# 02-MIC.net
KiCad netlist of a schematic drawn in Altium Designer
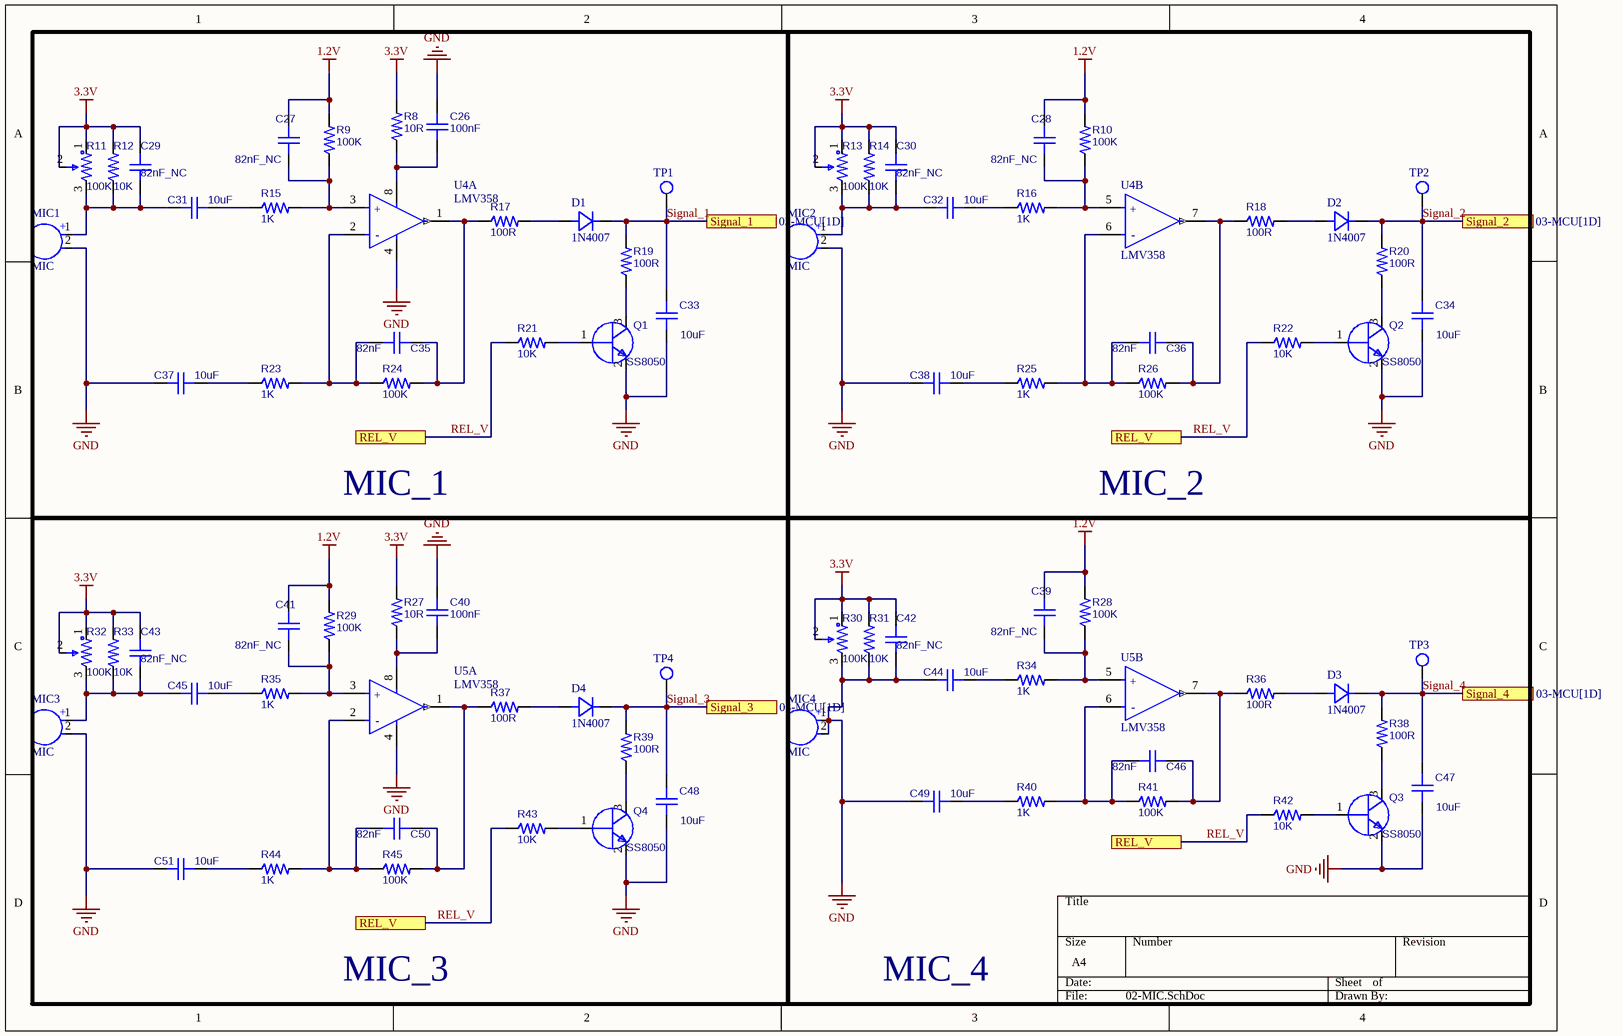
[diagram p0: 02-MIC.SchDoc]

(export (version "E")
  (design (tool "Eeschema 10.0.6"))
  (components
    (comp (ref "C26")
      (value "100nF")
      (footprint "CAP-SMD-0603")
      (description "贴片电容")
      (fields
        (field (name "BOM_MANUFACTURER PART") "CL03A104KQ3NNNC")
        (field (name "BOM_SUPPLIER PART") "C160831")
        (field (name "CONTRIBUTOR") "LCSC")
      )
      (libsource (lib "声源跟踪小车原理图库") (part "CAP"))
    )
    (comp (ref "C27")
      (value "82nF_NC")
      (footprint "CAP-SMD-0603")
      (description "贴片电容")
      (fields
        (field (name "BOM_MANUFACTURER PART") "CL03A104KQ3NNNC")
        (field (name "BOM_SUPPLIER PART") "C160831")
        (field (name "CONTRIBUTOR") "LCSC")
      )
      (libsource (lib "声源跟踪小车原理图库") (part "CAP"))
    )
    (comp (ref "C28")
      (value "82nF_NC")
      (footprint "CAP-SMD-0603")
      (description "贴片电容")
      (fields
        (field (name "BOM_MANUFACTURER PART") "CL03A104KQ3NNNC")
        (field (name "BOM_SUPPLIER PART") "C160831")
        (field (name "CONTRIBUTOR") "LCSC")
      )
      (libsource (lib "声源跟踪小车原理图库") (part "CAP"))
    )
    (comp (ref "C29")
      (value "82nF_NC")
      (footprint "CAP-SMD-0603")
      (description "贴片电容")
      (fields
        (field (name "BOM_MANUFACTURER PART") "CL03A104KQ3NNNC")
        (field (name "BOM_SUPPLIER PART") "C160831")
        (field (name "CONTRIBUTOR") "LCSC")
      )
      (libsource (lib "声源跟踪小车原理图库") (part "CAP"))
    )
    (comp (ref "C30")
      (value "82nF_NC")
      (footprint "CAP-SMD-0603")
      (description "贴片电容")
      (fields
        (field (name "BOM_MANUFACTURER PART") "CL03A104KQ3NNNC")
        (field (name "BOM_SUPPLIER PART") "C160831")
        (field (name "CONTRIBUTOR") "LCSC")
      )
      (libsource (lib "声源跟踪小车原理图库") (part "CAP"))
    )
    (comp (ref "C31")
      (value "10uF")
      (footprint "CAP-SMD-0603")
      (description "贴片电容")
      (fields
        (field (name "BOM_MANUFACTURER PART") "CL03A104KQ3NNNC")
        (field (name "BOM_SUPPLIER PART") "C160831")
        (field (name "CONTRIBUTOR") "LCSC")
      )
      (libsource (lib "声源跟踪小车原理图库") (part "CAP"))
    )
    (comp (ref "C32")
      (value "10uF")
      (footprint "CAP-SMD-0603")
      (description "贴片电容")
      (fields
        (field (name "BOM_MANUFACTURER PART") "CL03A104KQ3NNNC")
        (field (name "BOM_SUPPLIER PART") "C160831")
        (field (name "CONTRIBUTOR") "LCSC")
      )
      (libsource (lib "声源跟踪小车原理图库") (part "CAP"))
    )
    (comp (ref "C33")
      (value "10uF")
      (footprint "CAP-SMD-0603")
      (description "贴片电容")
      (fields
        (field (name "BOM_MANUFACTURER PART") "CL03A104KQ3NNNC")
        (field (name "BOM_SUPPLIER PART") "C160831")
        (field (name "CONTRIBUTOR") "LCSC")
      )
      (libsource (lib "声源跟踪小车原理图库") (part "CAP"))
    )
    (comp (ref "C34")
      (value "10uF")
      (footprint "CAP-SMD-0603")
      (description "贴片电容")
      (fields
        (field (name "BOM_MANUFACTURER PART") "CL03A104KQ3NNNC")
        (field (name "BOM_SUPPLIER PART") "C160831")
        (field (name "CONTRIBUTOR") "LCSC")
      )
      (libsource (lib "声源跟踪小车原理图库") (part "CAP"))
    )
    (comp (ref "C35")
      (value "82nF")
      (footprint "CAP-SMD-0603")
      (description "贴片电容")
      (fields
        (field (name "BOM_MANUFACTURER PART") "CL03A104KQ3NNNC")
        (field (name "BOM_SUPPLIER PART") "C160831")
        (field (name "CONTRIBUTOR") "LCSC")
      )
      (libsource (lib "声源跟踪小车原理图库") (part "CAP"))
    )
    (comp (ref "C36")
      (value "82nF")
      (footprint "CAP-SMD-0603")
      (description "贴片电容")
      (fields
        (field (name "BOM_MANUFACTURER PART") "CL03A104KQ3NNNC")
        (field (name "BOM_SUPPLIER PART") "C160831")
        (field (name "CONTRIBUTOR") "LCSC")
      )
      (libsource (lib "声源跟踪小车原理图库") (part "CAP"))
    )
    (comp (ref "C37")
      (value "10uF")
      (footprint "CAP-SMD-0603")
      (description "贴片电容")
      (fields
        (field (name "BOM_MANUFACTURER PART") "CL03A104KQ3NNNC")
        (field (name "BOM_SUPPLIER PART") "C160831")
        (field (name "CONTRIBUTOR") "LCSC")
      )
      (libsource (lib "声源跟踪小车原理图库") (part "CAP"))
    )
    (comp (ref "C38")
      (value "10uF")
      (footprint "CAP-SMD-0603")
      (description "贴片电容")
      (fields
        (field (name "BOM_MANUFACTURER PART") "CL03A104KQ3NNNC")
        (field (name "BOM_SUPPLIER PART") "C160831")
        (field (name "CONTRIBUTOR") "LCSC")
      )
      (libsource (lib "声源跟踪小车原理图库") (part "CAP"))
    )
    (comp (ref "C39")
      (value "82nF_NC")
      (footprint "CAP-SMD-0603")
      (description "贴片电容")
      (fields
        (field (name "BOM_MANUFACTURER PART") "CL03A104KQ3NNNC")
        (field (name "BOM_SUPPLIER PART") "C160831")
        (field (name "CONTRIBUTOR") "LCSC")
      )
      (libsource (lib "声源跟踪小车原理图库") (part "CAP"))
    )
    (comp (ref "C40")
      (value "100nF")
      (footprint "CAP-SMD-0603")
      (description "贴片电容")
      (fields
        (field (name "BOM_MANUFACTURER PART") "CL03A104KQ3NNNC")
        (field (name "BOM_SUPPLIER PART") "C160831")
        (field (name "CONTRIBUTOR") "LCSC")
      )
      (libsource (lib "声源跟踪小车原理图库") (part "CAP"))
    )
    (comp (ref "C41")
      (value "82nF_NC")
      (footprint "CAP-SMD-0603")
      (description "贴片电容")
      (fields
        (field (name "BOM_MANUFACTURER PART") "CL03A104KQ3NNNC")
        (field (name "BOM_SUPPLIER PART") "C160831")
        (field (name "CONTRIBUTOR") "LCSC")
      )
      (libsource (lib "声源跟踪小车原理图库") (part "CAP"))
    )
    (comp (ref "C42")
      (value "82nF_NC")
      (footprint "CAP-SMD-0603")
      (description "贴片电容")
      (fields
        (field (name "BOM_MANUFACTURER PART") "CL03A104KQ3NNNC")
        (field (name "BOM_SUPPLIER PART") "C160831")
        (field (name "CONTRIBUTOR") "LCSC")
      )
      (libsource (lib "声源跟踪小车原理图库") (part "CAP"))
    )
    (comp (ref "C43")
      (value "82nF_NC")
      (footprint "CAP-SMD-0603")
      (description "贴片电容")
      (fields
        (field (name "BOM_MANUFACTURER PART") "CL03A104KQ3NNNC")
        (field (name "BOM_SUPPLIER PART") "C160831")
        (field (name "CONTRIBUTOR") "LCSC")
      )
      (libsource (lib "声源跟踪小车原理图库") (part "CAP"))
    )
    (comp (ref "C44")
      (value "10uF")
      (footprint "CAP-SMD-0603")
      (description "贴片电容")
      (fields
        (field (name "BOM_MANUFACTURER PART") "CL03A104KQ3NNNC")
        (field (name "BOM_SUPPLIER PART") "C160831")
        (field (name "CONTRIBUTOR") "LCSC")
      )
      (libsource (lib "声源跟踪小车原理图库") (part "CAP"))
    )
    (comp (ref "C45")
      (value "10uF")
      (footprint "CAP-SMD-0603")
      (description "贴片电容")
      (fields
        (field (name "BOM_MANUFACTURER PART") "CL03A104KQ3NNNC")
        (field (name "BOM_SUPPLIER PART") "C160831")
        (field (name "CONTRIBUTOR") "LCSC")
      )
      (libsource (lib "声源跟踪小车原理图库") (part "CAP"))
    )
    (comp (ref "C46")
      (value "82nF")
      (footprint "CAP-SMD-0603")
      (description "贴片电容")
      (fields
        (field (name "BOM_MANUFACTURER PART") "CL03A104KQ3NNNC")
        (field (name "BOM_SUPPLIER PART") "C160831")
        (field (name "CONTRIBUTOR") "LCSC")
      )
      (libsource (lib "声源跟踪小车原理图库") (part "CAP"))
    )
    (comp (ref "C47")
      (value "10uF")
      (footprint "CAP-SMD-0603")
      (description "贴片电容")
      (fields
        (field (name "BOM_MANUFACTURER PART") "CL03A104KQ3NNNC")
        (field (name "BOM_SUPPLIER PART") "C160831")
        (field (name "CONTRIBUTOR") "LCSC")
      )
      (libsource (lib "声源跟踪小车原理图库") (part "CAP"))
    )
    (comp (ref "C48")
      (value "10uF")
      (footprint "CAP-SMD-0603")
      (description "贴片电容")
      (fields
        (field (name "BOM_MANUFACTURER PART") "CL03A104KQ3NNNC")
        (field (name "BOM_SUPPLIER PART") "C160831")
        (field (name "CONTRIBUTOR") "LCSC")
      )
      (libsource (lib "声源跟踪小车原理图库") (part "CAP"))
    )
    (comp (ref "C49")
      (value "10uF")
      (footprint "CAP-SMD-0603")
      (description "贴片电容")
      (fields
        (field (name "BOM_MANUFACTURER PART") "CL03A104KQ3NNNC")
        (field (name "BOM_SUPPLIER PART") "C160831")
        (field (name "CONTRIBUTOR") "LCSC")
      )
      (libsource (lib "声源跟踪小车原理图库") (part "CAP"))
    )
    (comp (ref "C50")
      (value "82nF")
      (footprint "CAP-SMD-0603")
      (description "贴片电容")
      (fields
        (field (name "BOM_MANUFACTURER PART") "CL03A104KQ3NNNC")
        (field (name "BOM_SUPPLIER PART") "C160831")
        (field (name "CONTRIBUTOR") "LCSC")
      )
      (libsource (lib "声源跟踪小车原理图库") (part "CAP"))
    )
    (comp (ref "C51")
      (value "10uF")
      (footprint "CAP-SMD-0603")
      (description "贴片电容")
      (fields
        (field (name "BOM_MANUFACTURER PART") "CL03A104KQ3NNNC")
        (field (name "BOM_SUPPLIER PART") "C160831")
        (field (name "CONTRIBUTOR") "LCSC")
      )
      (libsource (lib "声源跟踪小车原理图库") (part "CAP"))
    )
    (comp (ref "D1")
      (value "1N4007")
      (footprint "SOD-123-P3.4")
      (description "二极管1N4148W")
      (fields (field (name "MANUFACTURER") "PSI(宝力芯)") (field (name "MANUFACTURER PART") "1N4148W"))
      (libsource (lib "声源跟踪小车原理图库") (part "Diode"))
    )
    (comp (ref "D2")
      (value "1N4007")
      (footprint "SOD-123-P3.4")
      (description "二极管1N4148W")
      (fields (field (name "MANUFACTURER") "PSI(宝力芯)") (field (name "MANUFACTURER PART") "1N4148W"))
      (libsource (lib "声源跟踪小车原理图库") (part "Diode"))
    )
    (comp (ref "D3")
      (value "1N4007")
      (footprint "SOD-123-P3.4")
      (description "二极管1N4148W")
      (fields (field (name "MANUFACTURER") "PSI(宝力芯)") (field (name "MANUFACTURER PART") "1N4148W"))
      (libsource (lib "声源跟踪小车原理图库") (part "Diode"))
    )
    (comp (ref "D4")
      (value "1N4007")
      (footprint "SOD-123-P3.4")
      (description "二极管1N4148W")
      (fields (field (name "MANUFACTURER") "PSI(宝力芯)") (field (name "MANUFACTURER PART") "1N4148W"))
      (libsource (lib "声源跟踪小车原理图库") (part "Diode"))
    )
    (comp (ref "MIC1")
      (value "MIC")
      (footprint "MIC-TH-BD4.0-P1.4")
      (description "咪头MIC COND ANALOG OMNI -38DB")
      (libsource (lib "声源跟踪小车原理图库") (part "MIC"))
    )
    (comp (ref "MIC2")
      (value "MIC")
      (footprint "MIC-TH-BD4.0-P1.4")
      (description "咪头MIC COND ANALOG OMNI -38DB")
      (libsource (lib "声源跟踪小车原理图库") (part "MIC"))
    )
    (comp (ref "MIC3")
      (value "MIC")
      (footprint "MIC-TH-BD4.0-P1.4")
      (description "咪头MIC COND ANALOG OMNI -38DB")
      (libsource (lib "声源跟踪小车原理图库") (part "MIC"))
    )
    (comp (ref "MIC4")
      (value "MIC")
      (footprint "MIC-TH-BD4.0-P1.4")
      (description "咪头MIC COND ANALOG OMNI -38DB")
      (libsource (lib "声源跟踪小车原理图库") (part "MIC"))
    )
    (comp (ref "Q1")
      (value "SS8050")
      (footprint "SOT-23-3-LP2.28-P1.91")
      (description "贴片NPN三极管")
      (fields
        (field (name "BOM_SUPPLIER PART") "C2898668")
        (field (name "BOM_MANUFACTURER PART") "S9013")
        (field (name "CONTRIBUTOR") "LCSC")
      )
      (libsource (lib "声源跟踪小车原理图库") (part "NPN-SOT-23-3"))
    )
    (comp (ref "Q2")
      (value "SS8050")
      (footprint "SOT-23-3-LP2.28-P1.91")
      (description "贴片NPN三极管")
      (fields
        (field (name "BOM_SUPPLIER PART") "C2898668")
        (field (name "BOM_MANUFACTURER PART") "S9013")
        (field (name "CONTRIBUTOR") "LCSC")
      )
      (libsource (lib "声源跟踪小车原理图库") (part "NPN-SOT-23-3"))
    )
    (comp (ref "Q3")
      (value "SS8050")
      (footprint "SOT-23-3-LP2.28-P1.91")
      (description "贴片NPN三极管")
      (fields
        (field (name "BOM_SUPPLIER PART") "C2898668")
        (field (name "BOM_MANUFACTURER PART") "S9013")
        (field (name "CONTRIBUTOR") "LCSC")
      )
      (libsource (lib "声源跟踪小车原理图库") (part "NPN-SOT-23-3"))
    )
    (comp (ref "Q4")
      (value "SS8050")
      (footprint "SOT-23-3-LP2.28-P1.91")
      (description "贴片NPN三极管")
      (fields
        (field (name "BOM_SUPPLIER PART") "C2898668")
        (field (name "BOM_MANUFACTURER PART") "S9013")
        (field (name "CONTRIBUTOR") "LCSC")
      )
      (libsource (lib "声源跟踪小车原理图库") (part "NPN-SOT-23-3"))
    )
    (comp (ref "R8")
      (value "10R")
      (footprint "RES-SMD-0603")
      (description "贴片电阻")
      (fields
        (field (name "BOM_SUPPLIER PART") "C118966")
        (field (name "BOM_MANUFACTURER PART") "3362P-1-104")
        (field (name "CONTRIBUTOR") "LCSC")
      )
      (libsource (lib "声源跟踪小车原理图库") (part "RES"))
    )
    (comp (ref "R9")
      (value "100K")
      (footprint "RES-SMD-0603")
      (description "贴片电阻")
      (fields
        (field (name "BOM_SUPPLIER PART") "C118966")
        (field (name "BOM_MANUFACTURER PART") "3362P-1-104")
        (field (name "CONTRIBUTOR") "LCSC")
      )
      (libsource (lib "声源跟踪小车原理图库") (part "RES"))
    )
    (comp (ref "R10")
      (value "100K")
      (footprint "RES-SMD-0603")
      (description "贴片电阻")
      (fields
        (field (name "BOM_SUPPLIER PART") "C118966")
        (field (name "BOM_MANUFACTURER PART") "3362P-1-104")
        (field (name "CONTRIBUTOR") "LCSC")
      )
      (libsource (lib "声源跟踪小车原理图库") (part "RES"))
    )
    (comp (ref "R11")
      (value "100K")
      (footprint "RES-SMD-ADJ-3224W")
      (description "可调电阻,电位器")
      (fields
        (field (name "BOM_SUPPLIER PART") "C118966")
        (field (name "BOM_MANUFACTURER PART") "3362P-1-104")
        (field (name "CONTRIBUTOR") "LCSC")
      )
      (libsource (lib "声源跟踪小车原理图库") (part "RES-ADJ"))
    )
    (comp (ref "R12")
      (value "10K")
      (footprint "RES-SMD-0603")
      (description "贴片电阻")
      (fields
        (field (name "BOM_SUPPLIER PART") "C118966")
        (field (name "BOM_MANUFACTURER PART") "3362P-1-104")
        (field (name "CONTRIBUTOR") "LCSC")
      )
      (libsource (lib "声源跟踪小车原理图库") (part "RES"))
    )
    (comp (ref "R13")
      (value "100K")
      (footprint "RES-SMD-ADJ-3224W")
      (description "可调电阻,电位器")
      (fields
        (field (name "BOM_SUPPLIER PART") "C118966")
        (field (name "BOM_MANUFACTURER PART") "3362P-1-104")
        (field (name "CONTRIBUTOR") "LCSC")
      )
      (libsource (lib "声源跟踪小车原理图库") (part "RES-ADJ"))
    )
    (comp (ref "R14")
      (value "10K")
      (footprint "RES-SMD-0603")
      (description "贴片电阻")
      (fields
        (field (name "BOM_SUPPLIER PART") "C118966")
        (field (name "BOM_MANUFACTURER PART") "3362P-1-104")
        (field (name "CONTRIBUTOR") "LCSC")
      )
      (libsource (lib "声源跟踪小车原理图库") (part "RES"))
    )
    (comp (ref "R15")
      (value "1K")
      (footprint "RES-SMD-0603")
      (description "贴片电阻")
      (fields
        (field (name "BOM_SUPPLIER PART") "C118966")
        (field (name "BOM_MANUFACTURER PART") "3362P-1-104")
        (field (name "CONTRIBUTOR") "LCSC")
      )
      (libsource (lib "声源跟踪小车原理图库") (part "RES"))
    )
    (comp (ref "R16")
      (value "1K")
      (footprint "RES-SMD-0603")
      (description "贴片电阻")
      (fields
        (field (name "BOM_SUPPLIER PART") "C118966")
        (field (name "BOM_MANUFACTURER PART") "3362P-1-104")
        (field (name "CONTRIBUTOR") "LCSC")
      )
      (libsource (lib "声源跟踪小车原理图库") (part "RES"))
    )
    (comp (ref "R17")
      (value "100R")
      (footprint "RES-SMD-0603")
      (description "贴片电阻")
      (fields
        (field (name "BOM_SUPPLIER PART") "C118966")
        (field (name "BOM_MANUFACTURER PART") "3362P-1-104")
        (field (name "CONTRIBUTOR") "LCSC")
      )
      (libsource (lib "声源跟踪小车原理图库") (part "RES"))
    )
    (comp (ref "R18")
      (value "100R")
      (footprint "RES-SMD-0603")
      (description "贴片电阻")
      (fields
        (field (name "BOM_SUPPLIER PART") "C118966")
        (field (name "BOM_MANUFACTURER PART") "3362P-1-104")
        (field (name "CONTRIBUTOR") "LCSC")
      )
      (libsource (lib "声源跟踪小车原理图库") (part "RES"))
    )
    (comp (ref "R19")
      (value "100R")
      (footprint "RES-SMD-0603")
      (description "贴片电阻")
      (fields
        (field (name "BOM_SUPPLIER PART") "C118966")
        (field (name "BOM_MANUFACTURER PART") "3362P-1-104")
        (field (name "CONTRIBUTOR") "LCSC")
      )
      (libsource (lib "声源跟踪小车原理图库") (part "RES"))
    )
    (comp (ref "R20")
      (value "100R")
      (footprint "RES-SMD-0603")
      (description "贴片电阻")
      (fields
        (field (name "BOM_SUPPLIER PART") "C118966")
        (field (name "BOM_MANUFACTURER PART") "3362P-1-104")
        (field (name "CONTRIBUTOR") "LCSC")
      )
      (libsource (lib "声源跟踪小车原理图库") (part "RES"))
    )
    (comp (ref "R21")
      (value "10K")
      (footprint "RES-SMD-0603")
      (description "贴片电阻")
      (fields
        (field (name "BOM_SUPPLIER PART") "C118966")
        (field (name "BOM_MANUFACTURER PART") "3362P-1-104")
        (field (name "CONTRIBUTOR") "LCSC")
      )
      (libsource (lib "声源跟踪小车原理图库") (part "RES"))
    )
    (comp (ref "R22")
      (value "10K")
      (footprint "RES-SMD-0603")
      (description "贴片电阻")
      (fields
        (field (name "BOM_SUPPLIER PART") "C118966")
        (field (name "BOM_MANUFACTURER PART") "3362P-1-104")
        (field (name "CONTRIBUTOR") "LCSC")
      )
      (libsource (lib "声源跟踪小车原理图库") (part "RES"))
    )
    (comp (ref "R23")
      (value "1K")
      (footprint "RES-SMD-0603")
      (description "贴片电阻")
      (fields
        (field (name "BOM_SUPPLIER PART") "C118966")
        (field (name "BOM_MANUFACTURER PART") "3362P-1-104")
        (field (name "CONTRIBUTOR") "LCSC")
      )
      (libsource (lib "声源跟踪小车原理图库") (part "RES"))
    )
    (comp (ref "R24")
      (value "100K")
      (footprint "RES-SMD-0603")
      (description "贴片电阻")
      (fields
        (field (name "BOM_SUPPLIER PART") "C118966")
        (field (name "BOM_MANUFACTURER PART") "3362P-1-104")
        (field (name "CONTRIBUTOR") "LCSC")
      )
      (libsource (lib "声源跟踪小车原理图库") (part "RES"))
    )
    (comp (ref "R25")
      (value "1K")
      (footprint "RES-SMD-0603")
      (description "贴片电阻")
      (fields
        (field (name "BOM_SUPPLIER PART") "C118966")
        (field (name "BOM_MANUFACTURER PART") "3362P-1-104")
        (field (name "CONTRIBUTOR") "LCSC")
      )
      (libsource (lib "声源跟踪小车原理图库") (part "RES"))
    )
    (comp (ref "R26")
      (value "100K")
      (footprint "RES-SMD-0603")
      (description "贴片电阻")
      (fields
        (field (name "BOM_SUPPLIER PART") "C118966")
        (field (name "BOM_MANUFACTURER PART") "3362P-1-104")
        (field (name "CONTRIBUTOR") "LCSC")
      )
      (libsource (lib "声源跟踪小车原理图库") (part "RES"))
    )
    (comp (ref "R27")
      (value "10R")
      (footprint "RES-SMD-0603")
      (description "贴片电阻")
      (fields
        (field (name "BOM_SUPPLIER PART") "C118966")
        (field (name "BOM_MANUFACTURER PART") "3362P-1-104")
        (field (name "CONTRIBUTOR") "LCSC")
      )
      (libsource (lib "声源跟踪小车原理图库") (part "RES"))
    )
    (comp (ref "R28")
      (value "100K")
      (footprint "RES-SMD-0603")
      (description "贴片电阻")
      (fields
        (field (name "BOM_SUPPLIER PART") "C118966")
        (field (name "BOM_MANUFACTURER PART") "3362P-1-104")
        (field (name "CONTRIBUTOR") "LCSC")
      )
      (libsource (lib "声源跟踪小车原理图库") (part "RES"))
    )
    (comp (ref "R29")
      (value "100K")
      (footprint "RES-SMD-0603")
      (description "贴片电阻")
      (fields
        (field (name "BOM_SUPPLIER PART") "C118966")
        (field (name "BOM_MANUFACTURER PART") "3362P-1-104")
        (field (name "CONTRIBUTOR") "LCSC")
      )
      (libsource (lib "声源跟踪小车原理图库") (part "RES"))
    )
    (comp (ref "R30")
      (value "100K")
      (footprint "RES-SMD-ADJ-3224W")
      (description "可调电阻,电位器")
      (fields
        (field (name "BOM_SUPPLIER PART") "C118966")
        (field (name "BOM_MANUFACTURER PART") "3362P-1-104")
        (field (name "CONTRIBUTOR") "LCSC")
      )
      (libsource (lib "声源跟踪小车原理图库") (part "RES-ADJ"))
    )
    (comp (ref "R31")
      (value "10K")
      (footprint "RES-SMD-0603")
      (description "贴片电阻")
      (fields
        (field (name "BOM_SUPPLIER PART") "C118966")
        (field (name "BOM_MANUFACTURER PART") "3362P-1-104")
        (field (name "CONTRIBUTOR") "LCSC")
      )
      (libsource (lib "声源跟踪小车原理图库") (part "RES"))
    )
    (comp (ref "R32")
      (value "100K")
      (footprint "RES-SMD-ADJ-3224W")
      (description "可调电阻,电位器")
      (fields
        (field (name "BOM_SUPPLIER PART") "C118966")
        (field (name "BOM_MANUFACTURER PART") "3362P-1-104")
        (field (name "CONTRIBUTOR") "LCSC")
      )
      (libsource (lib "声源跟踪小车原理图库") (part "RES-ADJ"))
    )
    (comp (ref "R33")
      (value "10K")
      (footprint "RES-SMD-0603")
      (description "贴片电阻")
      (fields
        (field (name "BOM_SUPPLIER PART") "C118966")
        (field (name "BOM_MANUFACTURER PART") "3362P-1-104")
        (field (name "CONTRIBUTOR") "LCSC")
      )
      (libsource (lib "声源跟踪小车原理图库") (part "RES"))
    )
    (comp (ref "R34")
      (value "1K")
      (footprint "RES-SMD-0603")
      (description "贴片电阻")
      (fields
        (field (name "BOM_SUPPLIER PART") "C118966")
        (field (name "BOM_MANUFACTURER PART") "3362P-1-104")
        (field (name "CONTRIBUTOR") "LCSC")
      )
      (libsource (lib "声源跟踪小车原理图库") (part "RES"))
    )
    (comp (ref "R35")
      (value "1K")
      (footprint "RES-SMD-0603")
      (description "贴片电阻")
      (fields
        (field (name "BOM_SUPPLIER PART") "C118966")
        (field (name "BOM_MANUFACTURER PART") "3362P-1-104")
        (field (name "CONTRIBUTOR") "LCSC")
      )
      (libsource (lib "声源跟踪小车原理图库") (part "RES"))
    )
    (comp (ref "R36")
      (value "100R")
      (footprint "RES-SMD-0603")
      (description "贴片电阻")
      (fields
        (field (name "BOM_SUPPLIER PART") "C118966")
        (field (name "BOM_MANUFACTURER PART") "3362P-1-104")
        (field (name "CONTRIBUTOR") "LCSC")
      )
      (libsource (lib "声源跟踪小车原理图库") (part "RES"))
    )
    (comp (ref "R37")
      (value "100R")
      (footprint "RES-SMD-0603")
      (description "贴片电阻")
      (fields
        (field (name "BOM_SUPPLIER PART") "C118966")
        (field (name "BOM_MANUFACTURER PART") "3362P-1-104")
        (field (name "CONTRIBUTOR") "LCSC")
      )
      (libsource (lib "声源跟踪小车原理图库") (part "RES"))
    )
    (comp (ref "R38")
      (value "100R")
      (footprint "RES-SMD-0603")
      (description "贴片电阻")
      (fields
        (field (name "BOM_SUPPLIER PART") "C118966")
        (field (name "BOM_MANUFACTURER PART") "3362P-1-104")
        (field (name "CONTRIBUTOR") "LCSC")
      )
      (libsource (lib "声源跟踪小车原理图库") (part "RES"))
    )
    (comp (ref "R39")
      (value "100R")
      (footprint "RES-SMD-0603")
      (description "贴片电阻")
      (fields
        (field (name "BOM_SUPPLIER PART") "C118966")
        (field (name "BOM_MANUFACTURER PART") "3362P-1-104")
        (field (name "CONTRIBUTOR") "LCSC")
      )
      (libsource (lib "声源跟踪小车原理图库") (part "RES"))
    )
    (comp (ref "R40")
      (value "1K")
      (footprint "RES-SMD-0603")
      (description "贴片电阻")
      (fields
        (field (name "BOM_SUPPLIER PART") "C118966")
        (field (name "BOM_MANUFACTURER PART") "3362P-1-104")
        (field (name "CONTRIBUTOR") "LCSC")
      )
      (libsource (lib "声源跟踪小车原理图库") (part "RES"))
    )
    (comp (ref "R41")
      (value "100K")
      (footprint "RES-SMD-0603")
      (description "贴片电阻")
      (fields
        (field (name "BOM_SUPPLIER PART") "C118966")
        (field (name "BOM_MANUFACTURER PART") "3362P-1-104")
        (field (name "CONTRIBUTOR") "LCSC")
      )
      (libsource (lib "声源跟踪小车原理图库") (part "RES"))
    )
    (comp (ref "R42")
      (value "10K")
      (footprint "RES-SMD-0603")
      (description "贴片电阻")
      (fields
        (field (name "BOM_SUPPLIER PART") "C118966")
        (field (name "BOM_MANUFACTURER PART") "3362P-1-104")
        (field (name "CONTRIBUTOR") "LCSC")
      )
      (libsource (lib "声源跟踪小车原理图库") (part "RES"))
    )
    (comp (ref "R43")
      (value "10K")
      (footprint "RES-SMD-0603")
      (description "贴片电阻")
      (fields
        (field (name "BOM_SUPPLIER PART") "C118966")
        (field (name "BOM_MANUFACTURER PART") "3362P-1-104")
        (field (name "CONTRIBUTOR") "LCSC")
      )
      (libsource (lib "声源跟踪小车原理图库") (part "RES"))
    )
    (comp (ref "R44")
      (value "1K")
      (footprint "RES-SMD-0603")
      (description "贴片电阻")
      (fields
        (field (name "BOM_SUPPLIER PART") "C118966")
        (field (name "BOM_MANUFACTURER PART") "3362P-1-104")
        (field (name "CONTRIBUTOR") "LCSC")
      )
      (libsource (lib "声源跟踪小车原理图库") (part "RES"))
    )
    (comp (ref "R45")
      (value "100K")
      (footprint "RES-SMD-0603")
      (description "贴片电阻")
      (fields
        (field (name "BOM_SUPPLIER PART") "C118966")
        (field (name "BOM_MANUFACTURER PART") "3362P-1-104")
        (field (name "CONTRIBUTOR") "LCSC")
      )
      (libsource (lib "声源跟踪小车原理图库") (part "RES"))
    )
    (comp (ref "TP1")
      (value "TP")
      (footprint "TP")
      (description "TP测试点")
      (libsource (lib "声源跟踪小车原理图库") (part "TP"))
    )
    (comp (ref "TP2")
      (value "TP")
      (footprint "TP")
      (description "TP测试点")
      (libsource (lib "声源跟踪小车原理图库") (part "TP"))
    )
    (comp (ref "TP3")
      (value "TP")
      (footprint "TP")
      (description "TP测试点")
      (libsource (lib "声源跟踪小车原理图库") (part "TP"))
    )
    (comp (ref "TP4")
      (value "TP")
      (footprint "TP")
      (description "TP测试点")
      (libsource (lib "声源跟踪小车原理图库") (part "TP"))
    )
    (comp (ref "U4")
      (value "LMV358")
      (footprint "SOIC-8-LP5.5-P1.27")
      (description "运放IC OPAMP GP 2 CIRCUIT 8SOIC")
      (libsource (lib "声源跟踪小车原理图库") (part "LMV358"))
    )
    (comp (ref "U5")
      (value "LMV358")
      (footprint "SOIC-8-LP5.5-P1.27")
      (description "运放IC OPAMP GP 2 CIRCUIT 8SOIC")
      (libsource (lib "声源跟踪小车原理图库") (part "LMV358"))
    )
  )
  (nets
    (net (code "1") (name "/REL_V") (class "Default")
      (node (ref "R21") (pin "1") (pinfunction "1_1") (pintype "passive"))
      (node (ref "R22") (pin "1") (pinfunction "1_1") (pintype "passive"))
      (node (ref "R42") (pin "1") (pinfunction "1_1") (pintype "passive"))
      (node (ref "R43") (pin "1") (pinfunction "1_1") (pintype "passive"))
    )
    (net (code "2") (name "/Signal_1") (class "Default")
      (node (ref "C33") (pin "2") (pinfunction "2_2") (pintype "passive"))
      (node (ref "D1") (pin "2") (pinfunction "A_2") (pintype "passive"))
      (node (ref "R19") (pin "2") (pinfunction "2_2") (pintype "passive"))
      (node (ref "TP1") (pin "1") (pinfunction "1_1") (pintype "passive"))
    )
    (net (code "3") (name "/Signal_2") (class "Default")
      (node (ref "C34") (pin "2") (pinfunction "2_2") (pintype "passive"))
      (node (ref "D2") (pin "2") (pinfunction "A_2") (pintype "passive"))
      (node (ref "R20") (pin "2") (pinfunction "2_2") (pintype "passive"))
      (node (ref "TP2") (pin "1") (pinfunction "1_1") (pintype "passive"))
    )
    (net (code "4") (name "/Signal_3") (class "Default")
      (node (ref "C48") (pin "2") (pinfunction "2_2") (pintype "passive"))
      (node (ref "D4") (pin "2") (pinfunction "A_2") (pintype "passive"))
      (node (ref "R39") (pin "2") (pinfunction "2_2") (pintype "passive"))
      (node (ref "TP4") (pin "1") (pinfunction "1_1") (pintype "passive"))
    )
    (net (code "5") (name "/Signal_4") (class "Default")
      (node (ref "C47") (pin "2") (pinfunction "2_2") (pintype "passive"))
      (node (ref "D3") (pin "2") (pinfunction "A_2") (pintype "passive"))
      (node (ref "R38") (pin "2") (pinfunction "2_2") (pintype "passive"))
      (node (ref "TP3") (pin "1") (pinfunction "1_1") (pintype "passive"))
    )
    (net (code "6") (name "1.2V") (class "Default")
      (node (ref "C27") (pin "2") (pinfunction "2_2") (pintype "passive"))
      (node (ref "C28") (pin "2") (pinfunction "2_2") (pintype "passive"))
      (node (ref "C39") (pin "2") (pinfunction "2_2") (pintype "passive"))
      (node (ref "C41") (pin "2") (pinfunction "2_2") (pintype "passive"))
      (node (ref "R10") (pin "2") (pinfunction "2_2") (pintype "passive"))
      (node (ref "R28") (pin "2") (pinfunction "2_2") (pintype "passive"))
      (node (ref "R29") (pin "2") (pinfunction "2_2") (pintype "passive"))
      (node (ref "R9") (pin "2") (pinfunction "2_2") (pintype "passive"))
    )
    (net (code "7") (name "3.3V") (class "Default")
      (node (ref "C29") (pin "2") (pinfunction "2_2") (pintype "passive"))
      (node (ref "C30") (pin "2") (pinfunction "2_2") (pintype "passive"))
      (node (ref "C42") (pin "2") (pinfunction "2_2") (pintype "passive"))
      (node (ref "C43") (pin "2") (pinfunction "2_2") (pintype "passive"))
      (node (ref "R11") (pin "1") (pinfunction "1_1") (pintype "passive"))
      (node (ref "R11") (pin "2") (pinfunction "2_2") (pintype "passive"))
      (node (ref "R12") (pin "2") (pinfunction "2_2") (pintype "passive"))
      (node (ref "R13") (pin "1") (pinfunction "1_1") (pintype "passive"))
      (node (ref "R13") (pin "2") (pinfunction "2_2") (pintype "passive"))
      (node (ref "R14") (pin "2") (pinfunction "2_2") (pintype "passive"))
      (node (ref "R27") (pin "2") (pinfunction "2_2") (pintype "passive"))
      (node (ref "R30") (pin "1") (pinfunction "1_1") (pintype "passive"))
      (node (ref "R30") (pin "2") (pinfunction "2_2") (pintype "passive"))
      (node (ref "R31") (pin "2") (pinfunction "2_2") (pintype "passive"))
      (node (ref "R32") (pin "1") (pinfunction "1_1") (pintype "passive"))
      (node (ref "R32") (pin "2") (pinfunction "2_2") (pintype "passive"))
      (node (ref "R33") (pin "2") (pinfunction "2_2") (pintype "passive"))
      (node (ref "R8") (pin "2") (pinfunction "2_2") (pintype "passive"))
    )
    (net (code "8") (name "GND") (class "Default")
      (node (ref "C26") (pin "2") (pinfunction "2_2") (pintype "passive"))
      (node (ref "C33") (pin "1") (pinfunction "1_1") (pintype "passive"))
      (node (ref "C34") (pin "1") (pinfunction "1_1") (pintype "passive"))
      (node (ref "C37") (pin "1") (pinfunction "1_1") (pintype "passive"))
      (node (ref "C38") (pin "1") (pinfunction "1_1") (pintype "passive"))
      (node (ref "C40") (pin "2") (pinfunction "2_2") (pintype "passive"))
      (node (ref "C42") (pin "1") (pinfunction "1_1") (pintype "passive"))
      (node (ref "C44") (pin "1") (pinfunction "1_1") (pintype "passive"))
      (node (ref "C47") (pin "1") (pinfunction "1_1") (pintype "passive"))
      (node (ref "C48") (pin "1") (pinfunction "1_1") (pintype "passive"))
      (node (ref "C49") (pin "1") (pinfunction "1_1") (pintype "passive"))
      (node (ref "C51") (pin "1") (pinfunction "1_1") (pintype "passive"))
      (node (ref "MIC1") (pin "2") (pinfunction "C_2") (pintype "passive"))
      (node (ref "MIC2") (pin "2") (pinfunction "C_2") (pintype "passive"))
      (node (ref "MIC3") (pin "2") (pinfunction "C_2") (pintype "passive"))
      (node (ref "MIC4") (pin "1") (pinfunction "A_1") (pintype "passive"))
      (node (ref "MIC4") (pin "2") (pinfunction "C_2") (pintype "passive"))
      (node (ref "Q1") (pin "2") (pinfunction "E_2") (pintype "passive"))
      (node (ref "Q2") (pin "2") (pinfunction "E_2") (pintype "passive"))
      (node (ref "Q3") (pin "2") (pinfunction "E_2") (pintype "passive"))
      (node (ref "Q4") (pin "2") (pinfunction "E_2") (pintype "passive"))
      (node (ref "R30") (pin "3") (pinfunction "3_3") (pintype "passive"))
      (node (ref "R31") (pin "1") (pinfunction "1_1") (pintype "passive"))
      (node (ref "U4") (pin "4") (pinfunction "GND_4") (pintype "power_in"))
      (node (ref "U5") (pin "4") (pinfunction "GND_4") (pintype "power_in"))
    )
    (net (code "9") (name "Net-(C31-Pad2)") (class "Default")
      (node (ref "C31") (pin "2") (pinfunction "2_2") (pintype "passive"))
      (node (ref "R15") (pin "1") (pinfunction "1_1") (pintype "passive"))
    )
    (net (code "10") (name "Net-(C32-Pad2)") (class "Default")
      (node (ref "C32") (pin "2") (pinfunction "2_2") (pintype "passive"))
      (node (ref "R16") (pin "1") (pinfunction "1_1") (pintype "passive"))
    )
    (net (code "11") (name "Net-(C37-Pad2)") (class "Default")
      (node (ref "C37") (pin "2") (pinfunction "2_2") (pintype "passive"))
      (node (ref "R23") (pin "1") (pinfunction "1_1") (pintype "passive"))
    )
    (net (code "12") (name "Net-(C38-Pad2)") (class "Default")
      (node (ref "C38") (pin "2") (pinfunction "2_2") (pintype "passive"))
      (node (ref "R25") (pin "1") (pinfunction "1_1") (pintype "passive"))
    )
    (net (code "13") (name "Net-(C44-Pad2)") (class "Default")
      (node (ref "C44") (pin "2") (pinfunction "2_2") (pintype "passive"))
      (node (ref "R34") (pin "1") (pinfunction "1_1") (pintype "passive"))
    )
    (net (code "14") (name "Net-(C45-Pad2)") (class "Default")
      (node (ref "C45") (pin "2") (pinfunction "2_2") (pintype "passive"))
      (node (ref "R35") (pin "1") (pinfunction "1_1") (pintype "passive"))
    )
    (net (code "15") (name "Net-(C49-Pad2)") (class "Default")
      (node (ref "C49") (pin "2") (pinfunction "2_2") (pintype "passive"))
      (node (ref "R40") (pin "1") (pinfunction "1_1") (pintype "passive"))
    )
    (net (code "16") (name "Net-(C51-Pad2)") (class "Default")
      (node (ref "C51") (pin "2") (pinfunction "2_2") (pintype "passive"))
      (node (ref "R44") (pin "1") (pinfunction "1_1") (pintype "passive"))
    )
    (net (code "17") (name "Net-(D1-K)") (class "Default")
      (node (ref "D1") (pin "1") (pinfunction "K_1") (pintype "passive"))
      (node (ref "R17") (pin "2") (pinfunction "2_2") (pintype "passive"))
    )
    (net (code "18") (name "Net-(D2-K)") (class "Default")
      (node (ref "D2") (pin "1") (pinfunction "K_1") (pintype "passive"))
      (node (ref "R18") (pin "2") (pinfunction "2_2") (pintype "passive"))
    )
    (net (code "19") (name "Net-(D3-K)") (class "Default")
      (node (ref "D3") (pin "1") (pinfunction "K_1") (pintype "passive"))
      (node (ref "R36") (pin "2") (pinfunction "2_2") (pintype "passive"))
    )
    (net (code "20") (name "Net-(D4-K)") (class "Default")
      (node (ref "D4") (pin "1") (pinfunction "K_1") (pintype "passive"))
      (node (ref "R37") (pin "2") (pinfunction "2_2") (pintype "passive"))
    )
    (net (code "21") (name "Net-(MIC1-A)") (class "Default")
      (node (ref "C29") (pin "1") (pinfunction "1_1") (pintype "passive"))
      (node (ref "C31") (pin "1") (pinfunction "1_1") (pintype "passive"))
      (node (ref "MIC1") (pin "1") (pinfunction "A_1") (pintype "passive"))
      (node (ref "R11") (pin "3") (pinfunction "3_3") (pintype "passive"))
      (node (ref "R12") (pin "1") (pinfunction "1_1") (pintype "passive"))
    )
    (net (code "22") (name "Net-(MIC2-A)") (class "Default")
      (node (ref "C30") (pin "1") (pinfunction "1_1") (pintype "passive"))
      (node (ref "C32") (pin "1") (pinfunction "1_1") (pintype "passive"))
      (node (ref "MIC2") (pin "1") (pinfunction "A_1") (pintype "passive"))
      (node (ref "R13") (pin "3") (pinfunction "3_3") (pintype "passive"))
      (node (ref "R14") (pin "1") (pinfunction "1_1") (pintype "passive"))
    )
    (net (code "23") (name "Net-(MIC3-A)") (class "Default")
      (node (ref "C43") (pin "1") (pinfunction "1_1") (pintype "passive"))
      (node (ref "C45") (pin "1") (pinfunction "1_1") (pintype "passive"))
      (node (ref "MIC3") (pin "1") (pinfunction "A_1") (pintype "passive"))
      (node (ref "R32") (pin "3") (pinfunction "3_3") (pintype "passive"))
      (node (ref "R33") (pin "1") (pinfunction "1_1") (pintype "passive"))
    )
    (net (code "24") (name "Net-(Q1-B)") (class "Default")
      (node (ref "Q1") (pin "1") (pinfunction "B_1") (pintype "passive"))
      (node (ref "R21") (pin "2") (pinfunction "2_2") (pintype "passive"))
    )
    (net (code "25") (name "Net-(Q1-C)") (class "Default")
      (node (ref "Q1") (pin "3") (pinfunction "C_3") (pintype "passive"))
      (node (ref "R19") (pin "1") (pinfunction "1_1") (pintype "passive"))
    )
    (net (code "26") (name "Net-(Q2-B)") (class "Default")
      (node (ref "Q2") (pin "1") (pinfunction "B_1") (pintype "passive"))
      (node (ref "R22") (pin "2") (pinfunction "2_2") (pintype "passive"))
    )
    (net (code "27") (name "Net-(Q2-C)") (class "Default")
      (node (ref "Q2") (pin "3") (pinfunction "C_3") (pintype "passive"))
      (node (ref "R20") (pin "1") (pinfunction "1_1") (pintype "passive"))
    )
    (net (code "28") (name "Net-(Q3-B)") (class "Default")
      (node (ref "Q3") (pin "1") (pinfunction "B_1") (pintype "passive"))
      (node (ref "R42") (pin "2") (pinfunction "2_2") (pintype "passive"))
    )
    (net (code "29") (name "Net-(Q3-C)") (class "Default")
      (node (ref "Q3") (pin "3") (pinfunction "C_3") (pintype "passive"))
      (node (ref "R38") (pin "1") (pinfunction "1_1") (pintype "passive"))
    )
    (net (code "30") (name "Net-(Q4-B)") (class "Default")
      (node (ref "Q4") (pin "1") (pinfunction "B_1") (pintype "passive"))
      (node (ref "R43") (pin "2") (pinfunction "2_2") (pintype "passive"))
    )
    (net (code "31") (name "Net-(Q4-C)") (class "Default")
      (node (ref "Q4") (pin "3") (pinfunction "C_3") (pintype "passive"))
      (node (ref "R39") (pin "1") (pinfunction "1_1") (pintype "passive"))
    )
    (net (code "32") (name "Net-(U4A-1IN+)") (class "Default")
      (node (ref "C27") (pin "1") (pinfunction "1_1") (pintype "passive"))
      (node (ref "R15") (pin "2") (pinfunction "2_2") (pintype "passive"))
      (node (ref "R9") (pin "1") (pinfunction "1_1") (pintype "passive"))
      (node (ref "U4") (pin "3") (pinfunction "1IN+_3") (pintype "tri_state"))
    )
    (net (code "33") (name "Net-(U4A-1IN-)") (class "Default")
      (node (ref "C35") (pin "1") (pinfunction "1_1") (pintype "passive"))
      (node (ref "R23") (pin "2") (pinfunction "2_2") (pintype "passive"))
      (node (ref "R24") (pin "1") (pinfunction "1_1") (pintype "passive"))
      (node (ref "U4") (pin "2") (pinfunction "1IN-_2") (pintype "tri_state"))
    )
    (net (code "34") (name "Net-(U4A-OUT)") (class "Default")
      (node (ref "C35") (pin "2") (pinfunction "2_2") (pintype "passive"))
      (node (ref "R17") (pin "1") (pinfunction "1_1") (pintype "passive"))
      (node (ref "R24") (pin "2") (pinfunction "2_2") (pintype "passive"))
      (node (ref "U4") (pin "1") (pinfunction "OUT_1") (pintype "output"))
    )
    (net (code "35") (name "Net-(U4A-VCC+)") (class "Default")
      (node (ref "C26") (pin "1") (pinfunction "1_1") (pintype "passive"))
      (node (ref "R8") (pin "1") (pinfunction "1_1") (pintype "passive"))
      (node (ref "U4") (pin "8") (pinfunction "VCC+_8") (pintype "power_in"))
    )
    (net (code "36") (name "Net-(U4B-1IN+)") (class "Default")
      (node (ref "C28") (pin "1") (pinfunction "1_1") (pintype "passive"))
      (node (ref "R10") (pin "1") (pinfunction "1_1") (pintype "passive"))
      (node (ref "R16") (pin "2") (pinfunction "2_2") (pintype "passive"))
      (node (ref "U4") (pin "5") (pinfunction "1IN+_5") (pintype "tri_state"))
    )
    (net (code "37") (name "Net-(U4B-1IN-)") (class "Default")
      (node (ref "C36") (pin "1") (pinfunction "1_1") (pintype "passive"))
      (node (ref "R25") (pin "2") (pinfunction "2_2") (pintype "passive"))
      (node (ref "R26") (pin "1") (pinfunction "1_1") (pintype "passive"))
      (node (ref "U4") (pin "6") (pinfunction "1IN-_6") (pintype "tri_state"))
    )
    (net (code "38") (name "Net-(U4B-OUT)") (class "Default")
      (node (ref "C36") (pin "2") (pinfunction "2_2") (pintype "passive"))
      (node (ref "R18") (pin "1") (pinfunction "1_1") (pintype "passive"))
      (node (ref "R26") (pin "2") (pinfunction "2_2") (pintype "passive"))
      (node (ref "U4") (pin "7") (pinfunction "OUT_7") (pintype "output"))
    )
    (net (code "39") (name "Net-(U5A-1IN+)") (class "Default")
      (node (ref "C41") (pin "1") (pinfunction "1_1") (pintype "passive"))
      (node (ref "R29") (pin "1") (pinfunction "1_1") (pintype "passive"))
      (node (ref "R35") (pin "2") (pinfunction "2_2") (pintype "passive"))
      (node (ref "U5") (pin "3") (pinfunction "1IN+_3") (pintype "tri_state"))
    )
    (net (code "40") (name "Net-(U5A-1IN-)") (class "Default")
      (node (ref "C50") (pin "1") (pinfunction "1_1") (pintype "passive"))
      (node (ref "R44") (pin "2") (pinfunction "2_2") (pintype "passive"))
      (node (ref "R45") (pin "1") (pinfunction "1_1") (pintype "passive"))
      (node (ref "U5") (pin "2") (pinfunction "1IN-_2") (pintype "tri_state"))
    )
    (net (code "41") (name "Net-(U5A-OUT)") (class "Default")
      (node (ref "C50") (pin "2") (pinfunction "2_2") (pintype "passive"))
      (node (ref "R37") (pin "1") (pinfunction "1_1") (pintype "passive"))
      (node (ref "R45") (pin "2") (pinfunction "2_2") (pintype "passive"))
      (node (ref "U5") (pin "1") (pinfunction "OUT_1") (pintype "output"))
    )
    (net (code "42") (name "Net-(U5A-VCC+)") (class "Default")
      (node (ref "C40") (pin "1") (pinfunction "1_1") (pintype "passive"))
      (node (ref "R27") (pin "1") (pinfunction "1_1") (pintype "passive"))
      (node (ref "U5") (pin "8") (pinfunction "VCC+_8") (pintype "power_in"))
    )
    (net (code "43") (name "Net-(U5B-1IN+)") (class "Default")
      (node (ref "C39") (pin "1") (pinfunction "1_1") (pintype "passive"))
      (node (ref "R28") (pin "1") (pinfunction "1_1") (pintype "passive"))
      (node (ref "R34") (pin "2") (pinfunction "2_2") (pintype "passive"))
      (node (ref "U5") (pin "5") (pinfunction "1IN+_5") (pintype "tri_state"))
    )
    (net (code "44") (name "Net-(U5B-1IN-)") (class "Default")
      (node (ref "C46") (pin "1") (pinfunction "1_1") (pintype "passive"))
      (node (ref "R40") (pin "2") (pinfunction "2_2") (pintype "passive"))
      (node (ref "R41") (pin "1") (pinfunction "1_1") (pintype "passive"))
      (node (ref "U5") (pin "6") (pinfunction "1IN-_6") (pintype "tri_state"))
    )
    (net (code "45") (name "Net-(U5B-OUT)") (class "Default")
      (node (ref "C46") (pin "2") (pinfunction "2_2") (pintype "passive"))
      (node (ref "R36") (pin "1") (pinfunction "1_1") (pintype "passive"))
      (node (ref "R41") (pin "2") (pinfunction "2_2") (pintype "passive"))
      (node (ref "U5") (pin "7") (pinfunction "OUT_7") (pintype "output"))
    )
  )
)
